# Battery_Board_v3_0.net
KiCad netlist of a schematic drawn in EAGLE
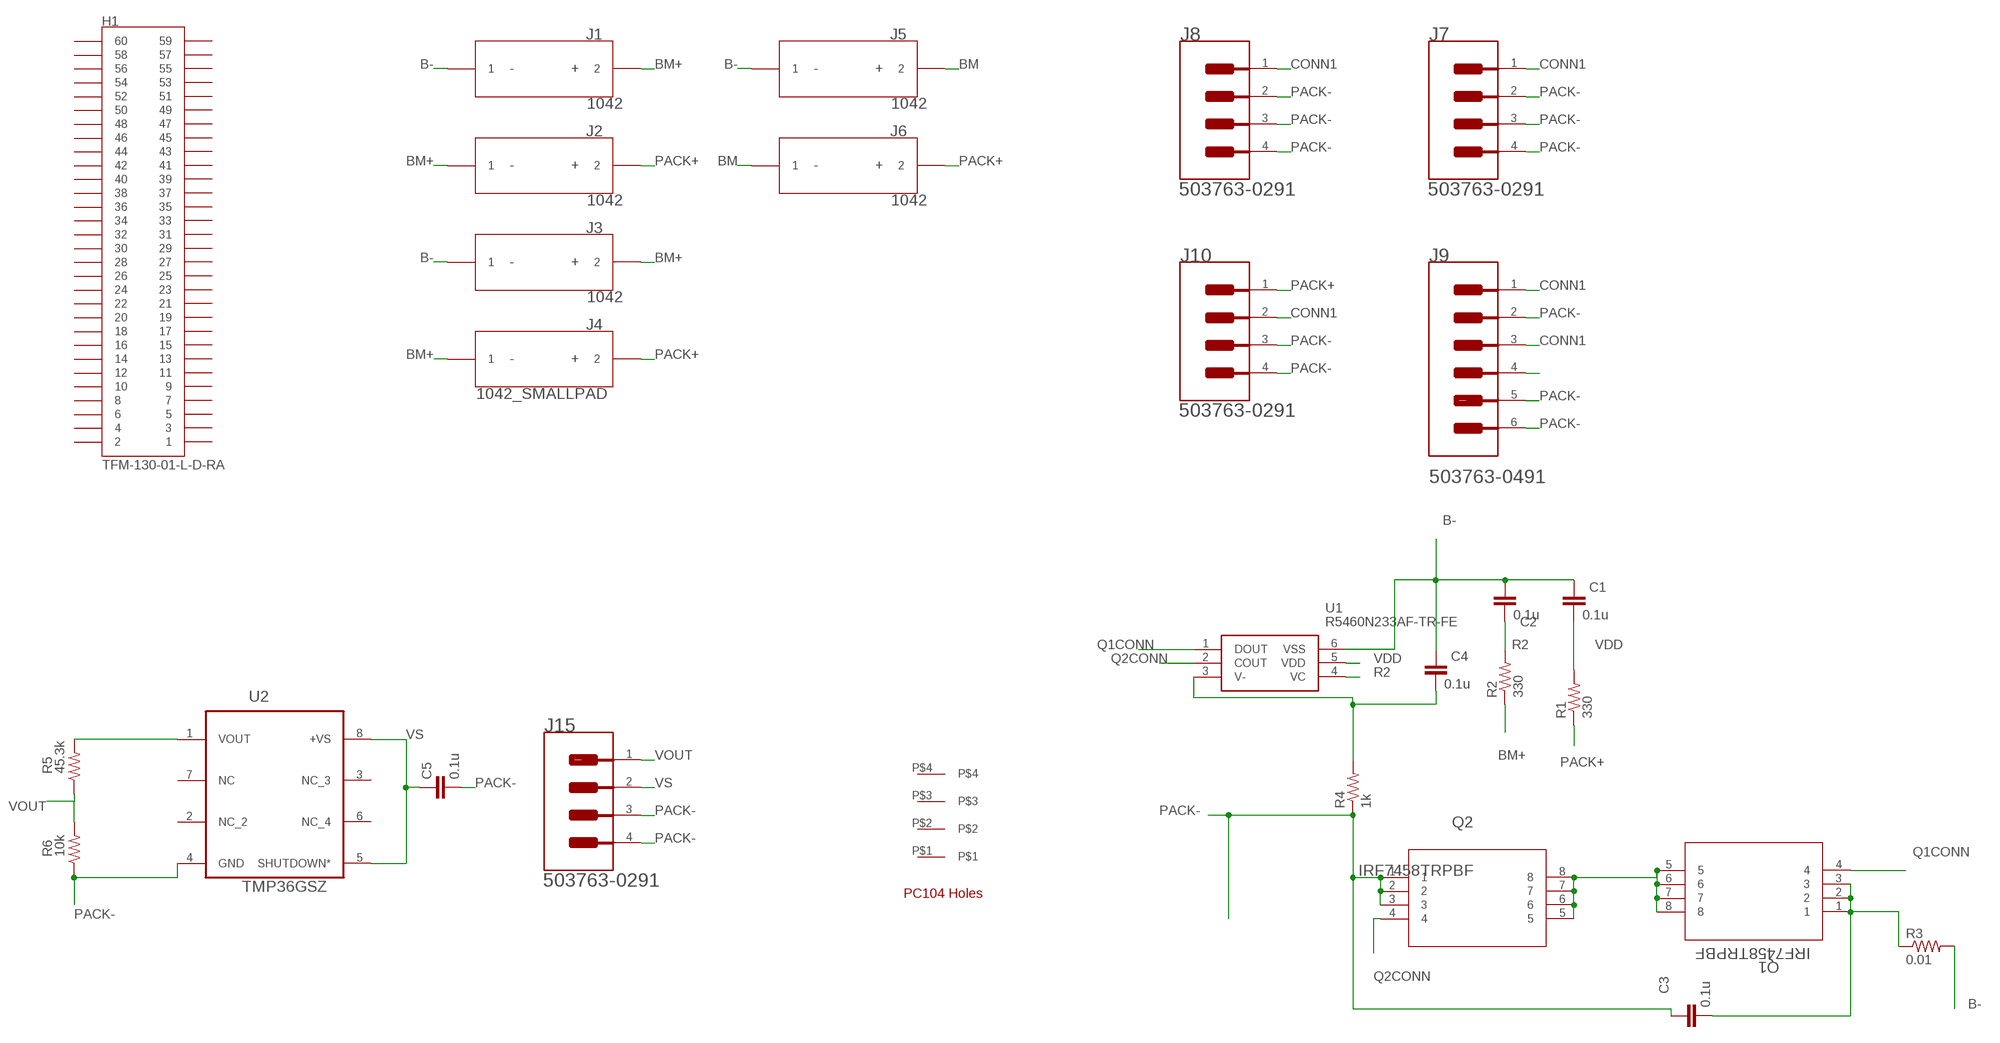
[diagram p0: schematic, sheet 1]

(export (version "E")
  (design (tool "Eeschema 10.0.6"))
  (components
    (comp (ref "C1")
      (value "0.1u")
      (footprint "eagle-import:0603-CAP")
      (libsource (lib "eagle-import") (part "CAP0603-CAP"))
    )
    (comp (ref "C2")
      (value "0.1u")
      (footprint "eagle-import:0603-CAP")
      (libsource (lib "eagle-import") (part "CAP0603-CAP"))
    )
    (comp (ref "C3")
      (value "0.1u")
      (footprint "eagle-import:0603-CAP")
      (libsource (lib "eagle-import") (part "CAP0603-CAP"))
    )
    (comp (ref "C4")
      (value "0.1u")
      (footprint "eagle-import:0603-CAP")
      (libsource (lib "eagle-import") (part "CAP0603-CAP"))
    )
    (comp (ref "C5")
      (value "0.1u")
      (footprint "eagle-import:0805")
      (libsource (lib "eagle-import") (part "CAP0805"))
    )
    (comp (ref "H1")
      (value "TFM-130-01-L-D-RA")
      (footprint "eagle-import:60_PIN")
      (libsource (lib "eagle-import") (part "TFM-130-01-L-D-RA"))
    )
    (comp (ref "J1")
      (value "1042")
      (footprint "eagle-import:1042_KEY")
      (fields (field (name "COPYRIGHT") "Copyright (C) 2021 Ultra Librarian. All rights reserved."))
      (libsource (lib "eagle-import") (part "1042"))
    )
    (comp (ref "J2")
      (value "1042")
      (footprint "eagle-import:1042_KEY")
      (fields (field (name "COPYRIGHT") "Copyright (C) 2021 Ultra Librarian. All rights reserved."))
      (libsource (lib "eagle-import") (part "1042"))
    )
    (comp (ref "J3")
      (value "1042")
      (footprint "eagle-import:1042_KEY")
      (fields (field (name "COPYRIGHT") "Copyright (C) 2021 Ultra Librarian. All rights reserved."))
      (libsource (lib "eagle-import") (part "1042"))
    )
    (comp (ref "J4")
      (value "1042_SMALLPAD")
      (footprint "eagle-import:1042_KEY_SMALLPAD")
      (libsource (lib "eagle-import") (part "1042_SMALLPAD"))
    )
    (comp (ref "J5")
      (value "1042")
      (footprint "eagle-import:1042_KEY")
      (fields (field (name "COPYRIGHT") "Copyright (C) 2021 Ultra Librarian. All rights reserved."))
      (libsource (lib "eagle-import") (part "1042"))
    )
    (comp (ref "J6")
      (value "1042")
      (footprint "eagle-import:1042_KEY")
      (fields (field (name "COPYRIGHT") "Copyright (C) 2021 Ultra Librarian. All rights reserved."))
      (libsource (lib "eagle-import") (part "1042"))
    )
    (comp (ref "J7")
      (value "MOLEX_503763-0291MOLEX_503763-0291_0_0")
      (footprint "eagle-import:MOLEX_503763-0291_0")
      (fields
        (field (name "DIGIKEY_PART_NUMBER") "WM10654CT-ND")
        (field (name "MF") "Molex")
        (field (name "MOUSER_PART_NUMBER") "538-503763-0291")
      )
      (libsource (lib "eagle-import") (part "MOLEX_503763-0291MOLEX_503763-0291_0_0"))
    )
    (comp (ref "J8")
      (value "MOLEX_503763-0291MOLEX_503763-0291_0_0")
      (footprint "eagle-import:MOLEX_503763-0291_0")
      (fields
        (field (name "DIGIKEY_PART_NUMBER") "WM10654CT-ND")
        (field (name "MF") "Molex")
        (field (name "MOUSER_PART_NUMBER") "538-503763-0291")
      )
      (libsource (lib "eagle-import") (part "MOLEX_503763-0291MOLEX_503763-0291_0_0"))
    )
    (comp (ref "J9")
      (value "MOLEX_503763-0491MOLEX_503763-0491_0_0")
      (footprint "eagle-import:MOLEX_503763-0491_0")
      (fields
        (field (name "DIGIKEY_PART_NUMBER") "WM10655CT-ND")
        (field (name "MF") "Molex")
        (field (name "MOUSER_PART_NUMBER") "538-503763-0491")
      )
      (libsource (lib "eagle-import") (part "MOLEX_503763-0491MOLEX_503763-0491_0_0"))
    )
    (comp (ref "J10")
      (value "MOLEX_503763-0291MOLEX_503763-0291_0_0")
      (footprint "eagle-import:MOLEX_503763-0291_0")
      (fields
        (field (name "DIGIKEY_PART_NUMBER") "WM10654CT-ND")
        (field (name "MF") "Molex")
        (field (name "MOUSER_PART_NUMBER") "538-503763-0291")
      )
      (libsource (lib "eagle-import") (part "MOLEX_503763-0291MOLEX_503763-0291_0_0"))
    )
    (comp (ref "J15")
      (value "MOLEX_503763-0291MOLEX_503763-0291_0_0")
      (footprint "eagle-import:MOLEX_503763-0291_0")
      (fields
        (field (name "DIGIKEY_PART_NUMBER") "WM10654CT-ND")
        (field (name "MF") "Molex")
        (field (name "MOUSER_PART_NUMBER") "538-503763-0291")
      )
      (libsource (lib "eagle-import") (part "MOLEX_503763-0291MOLEX_503763-0291_0_0"))
    )
    (comp (ref "Q1")
      (value "IRF7458TRPBF")
      (footprint "eagle-import:SO-8_IRF7458_3P9X4P9_INF")
      (fields (field (name "COPYRIGHT") "Copyright (C) 2021 Ultra Librarian. All rights reserved."))
      (libsource (lib "eagle-import") (part "IRF7458TRPBF"))
    )
    (comp (ref "Q2")
      (value "IRF7458TRPBF")
      (footprint "eagle-import:SO-8_IRF7458_3P9X4P9_INF")
      (fields (field (name "COPYRIGHT") "Copyright (C) 2021 Ultra Librarian. All rights reserved."))
      (libsource (lib "eagle-import") (part "IRF7458TRPBF"))
    )
    (comp (ref "R1")
      (value "330")
      (footprint "eagle-import:0603-RES")
      (libsource (lib "eagle-import") (part "RESISTOR0603-RES"))
    )
    (comp (ref "R2")
      (value "330")
      (footprint "eagle-import:0603-RES")
      (libsource (lib "eagle-import") (part "RESISTOR0603-RES"))
    )
    (comp (ref "R3")
      (value "0.01")
      (footprint "eagle-import:R2512")
      (libsource (lib "eagle-import") (part "RESISTOR2512"))
    )
    (comp (ref "R4")
      (value "1k")
      (footprint "eagle-import:0603-RES")
      (libsource (lib "eagle-import") (part "RESISTOR0603-RES"))
    )
    (comp (ref "R5")
      (value "45.3k")
      (footprint "eagle-import:0805")
      (libsource (lib "eagle-import") (part "RESISTOR0805-RES"))
    )
    (comp (ref "R6")
      (value "10k")
      (footprint "eagle-import:0805")
      (libsource (lib "eagle-import") (part "RESISTOR0805-RES"))
    )
    (comp (ref "U$1")
      (value "PC104_HOLES")
      (footprint "eagle-import:PC104_HOLES")
      (libsource (lib "eagle-import") (part "PC104_HOLES"))
    )
    (comp (ref "U1")
      (value "R5460N233AF-TR-FE")
      (footprint "eagle-import:SOT95P280X140-6N")
      (fields (field (name "MOUSER_PART_NUMBER") "848-R5460N233AFTRFE"))
      (libsource (lib "eagle-import") (part "R5460N233AF-TR-FE"))
    )
    (comp (ref "U2")
      (value "TMP36GSZ")
      (footprint "eagle-import:SOIC127P600X175-8N")
      (fields (field (name "MF") "Analog Devices"))
      (libsource (lib "eagle-import") (part "TMP36GSZ"))
    )
  )
  (nets
    (net (code "1") (name "/B-") (class "Default")
      (node (ref "C1") (pin "1") (pinfunction "1_1") (pintype "passive"))
      (node (ref "C2") (pin "1") (pinfunction "1_1") (pintype "passive"))
      (node (ref "C4") (pin "1") (pinfunction "1_1") (pintype "passive"))
      (node (ref "J1") (pin "1") (pinfunction "1_1") (pintype "passive"))
      (node (ref "J3") (pin "1") (pinfunction "1_1") (pintype "passive"))
      (node (ref "J5") (pin "1") (pinfunction "1_1") (pintype "passive"))
      (node (ref "R3") (pin "2") (pinfunction "2_2") (pintype "passive"))
      (node (ref "U1") (pin "6") (pinfunction "VSS_6") (pintype "bidirectional"))
    )
    (net (code "2") (name "/BM") (class "Default")
      (node (ref "J5") (pin "2") (pinfunction "2_2") (pintype "passive"))
      (node (ref "J6") (pin "1") (pinfunction "1_1") (pintype "passive"))
    )
    (net (code "3") (name "/BM+") (class "Default")
      (node (ref "J1") (pin "2") (pinfunction "2_2") (pintype "passive"))
      (node (ref "J2") (pin "1") (pinfunction "1_1") (pintype "passive"))
      (node (ref "J3") (pin "2") (pinfunction "2_2") (pintype "passive"))
      (node (ref "J4") (pin "1") (pinfunction "1_1") (pintype "passive"))
      (node (ref "R2") (pin "1") (pinfunction "1_1") (pintype "passive"))
    )
    (net (code "4") (name "/CONN1") (class "Default")
      (node (ref "J10") (pin "2") (pinfunction "2_2") (pintype "bidirectional"))
      (node (ref "J7") (pin "1") (pinfunction "1_1") (pintype "bidirectional"))
      (node (ref "J8") (pin "1") (pinfunction "1_1") (pintype "bidirectional"))
      (node (ref "J9") (pin "1") (pinfunction "1_1") (pintype "passive"))
      (node (ref "J9") (pin "3") (pinfunction "3_3") (pintype "passive"))
    )
    (net (code "5") (name "/PACK+") (class "Default")
      (node (ref "J10") (pin "1") (pinfunction "1_1") (pintype "bidirectional"))
      (node (ref "J2") (pin "2") (pinfunction "2_2") (pintype "passive"))
      (node (ref "J4") (pin "2") (pinfunction "2_2") (pintype "passive"))
      (node (ref "J6") (pin "2") (pinfunction "2_2") (pintype "passive"))
      (node (ref "R1") (pin "1") (pinfunction "1_1") (pintype "passive"))
    )
    (net (code "6") (name "/PACK-") (class "Default")
      (node (ref "C3") (pin "1") (pinfunction "1_1") (pintype "passive"))
      (node (ref "C5") (pin "2") (pinfunction "2_2") (pintype "passive"))
      (node (ref "J10") (pin "3") (pinfunction "MNT_1_3") (pintype "bidirectional"))
      (node (ref "J10") (pin "4") (pinfunction "MNT_2_4") (pintype "bidirectional"))
      (node (ref "J15") (pin "3") (pinfunction "MNT_1_3") (pintype "bidirectional"))
      (node (ref "J15") (pin "4") (pinfunction "MNT_2_4") (pintype "bidirectional"))
      (node (ref "J7") (pin "2") (pinfunction "2_2") (pintype "bidirectional"))
      (node (ref "J7") (pin "3") (pinfunction "MNT_1_3") (pintype "bidirectional"))
      (node (ref "J7") (pin "4") (pinfunction "MNT_2_4") (pintype "bidirectional"))
      (node (ref "J8") (pin "2") (pinfunction "2_2") (pintype "bidirectional"))
      (node (ref "J8") (pin "3") (pinfunction "MNT_1_3") (pintype "bidirectional"))
      (node (ref "J8") (pin "4") (pinfunction "MNT_2_4") (pintype "bidirectional"))
      (node (ref "J9") (pin "2") (pinfunction "2_2") (pintype "passive"))
      (node (ref "J9") (pin "4") (pinfunction "4_4") (pintype "passive"))
      (node (ref "J9") (pin "5") (pinfunction "MNT_1_5") (pintype "passive"))
      (node (ref "J9") (pin "6") (pinfunction "MNT_2_6") (pintype "passive"))
      (node (ref "Q2") (pin "1") (pinfunction "1_1") (pintype "passive"))
      (node (ref "Q2") (pin "2") (pinfunction "2_2") (pintype "passive"))
      (node (ref "Q2") (pin "3") (pinfunction "3_3") (pintype "passive"))
      (node (ref "R4") (pin "1") (pinfunction "1_1") (pintype "passive"))
      (node (ref "R6") (pin "1") (pinfunction "1_1") (pintype "passive"))
      (node (ref "U2") (pin "4") (pinfunction "GND_4") (pintype "passive"))
    )
    (net (code "7") (name "/Q1CONN") (class "Default")
      (node (ref "Q1") (pin "4") (pinfunction "4_4") (pintype "passive"))
      (node (ref "U1") (pin "1") (pinfunction "DOUT_1") (pintype "bidirectional"))
    )
    (net (code "8") (name "/Q2CONN") (class "Default")
      (node (ref "Q2") (pin "4") (pinfunction "4_4") (pintype "passive"))
      (node (ref "U1") (pin "2") (pinfunction "COUT_2") (pintype "bidirectional"))
    )
    (net (code "9") (name "/R2") (class "Default")
      (node (ref "C2") (pin "2") (pinfunction "2_2") (pintype "passive"))
      (node (ref "R2") (pin "2") (pinfunction "2_2") (pintype "passive"))
      (node (ref "U1") (pin "4") (pinfunction "VC_4") (pintype "bidirectional"))
    )
    (net (code "10") (name "/VDD") (class "Default")
      (node (ref "C1") (pin "2") (pinfunction "2_2") (pintype "passive"))
      (node (ref "R1") (pin "2") (pinfunction "2_2") (pintype "passive"))
      (node (ref "U1") (pin "5") (pinfunction "VDD_5") (pintype "bidirectional"))
    )
    (net (code "11") (name "/VOUT") (class "Default")
      (node (ref "J15") (pin "1") (pinfunction "1_1") (pintype "bidirectional"))
      (node (ref "R5") (pin "1") (pinfunction "1_1") (pintype "passive"))
      (node (ref "R6") (pin "2") (pinfunction "2_2") (pintype "passive"))
    )
    (net (code "12") (name "/VS") (class "Default")
      (node (ref "C5") (pin "1") (pinfunction "1_1") (pintype "passive"))
      (node (ref "J15") (pin "2") (pinfunction "2_2") (pintype "bidirectional"))
      (node (ref "U2") (pin "5") (pinfunction "SHUTDOWN*_5") (pintype "passive"))
      (node (ref "U2") (pin "8") (pinfunction "+VS_8") (pintype "power_in"))
    )
    (net (code "13") (name "Net-(C3-Pad2)") (class "Default")
      (node (ref "C3") (pin "2") (pinfunction "2_2") (pintype "passive"))
      (node (ref "Q1") (pin "1") (pinfunction "1_1") (pintype "passive"))
      (node (ref "Q1") (pin "2") (pinfunction "2_2") (pintype "passive"))
      (node (ref "Q1") (pin "3") (pinfunction "3_3") (pintype "passive"))
      (node (ref "R3") (pin "1") (pinfunction "1_1") (pintype "passive"))
    )
    (net (code "14") (name "Net-(Q1-Pad5)") (class "Default")
      (node (ref "Q1") (pin "5") (pinfunction "5_5") (pintype "passive"))
      (node (ref "Q1") (pin "6") (pinfunction "6_6") (pintype "passive"))
      (node (ref "Q1") (pin "7") (pinfunction "7_7") (pintype "passive"))
      (node (ref "Q1") (pin "8") (pinfunction "8_8") (pintype "passive"))
      (node (ref "Q2") (pin "5") (pinfunction "5_5") (pintype "passive"))
      (node (ref "Q2") (pin "6") (pinfunction "6_6") (pintype "passive"))
      (node (ref "Q2") (pin "7") (pinfunction "7_7") (pintype "passive"))
      (node (ref "Q2") (pin "8") (pinfunction "8_8") (pintype "passive"))
    )
    (net (code "15") (name "Net-(U1-V-)") (class "Default")
      (node (ref "C4") (pin "2") (pinfunction "2_2") (pintype "passive"))
      (node (ref "R4") (pin "2") (pinfunction "2_2") (pintype "passive"))
      (node (ref "U1") (pin "3") (pinfunction "V-_3") (pintype "bidirectional"))
    )
    (net (code "16") (name "Net-(U2-VOUT)") (class "Default")
      (node (ref "R5") (pin "2") (pinfunction "2_2") (pintype "passive"))
      (node (ref "U2") (pin "1") (pinfunction "VOUT_1") (pintype "passive"))
    )
    (net (code "17") (name "unconnected-(H1-Pad1)") (class "Default")
      (node (ref "H1") (pin "1") (pinfunction "1_1") (pintype "bidirectional"))
    )
    (net (code "18") (name "unconnected-(H1-Pad2)") (class "Default")
      (node (ref "H1") (pin "2") (pinfunction "2_2") (pintype "bidirectional"))
    )
    (net (code "19") (name "unconnected-(H1-Pad3)") (class "Default")
      (node (ref "H1") (pin "3") (pinfunction "3_3") (pintype "bidirectional"))
    )
    (net (code "20") (name "unconnected-(H1-Pad4)") (class "Default")
      (node (ref "H1") (pin "4") (pinfunction "4_4") (pintype "bidirectional"))
    )
    (net (code "21") (name "unconnected-(H1-Pad5)") (class "Default")
      (node (ref "H1") (pin "5") (pinfunction "5_5") (pintype "bidirectional"))
    )
    (net (code "22") (name "unconnected-(H1-Pad6)") (class "Default")
      (node (ref "H1") (pin "6") (pinfunction "6_6") (pintype "bidirectional"))
    )
    (net (code "23") (name "unconnected-(H1-Pad7)") (class "Default")
      (node (ref "H1") (pin "7") (pinfunction "7_7") (pintype "bidirectional"))
    )
    (net (code "24") (name "unconnected-(H1-Pad8)") (class "Default")
      (node (ref "H1") (pin "8") (pinfunction "8_8") (pintype "bidirectional"))
    )
    (net (code "25") (name "unconnected-(H1-Pad9)") (class "Default")
      (node (ref "H1") (pin "9") (pinfunction "9_9") (pintype "bidirectional"))
    )
    (net (code "26") (name "unconnected-(H1-Pad10)") (class "Default")
      (node (ref "H1") (pin "10") (pinfunction "10_10") (pintype "bidirectional"))
    )
    (net (code "27") (name "unconnected-(H1-Pad11)") (class "Default")
      (node (ref "H1") (pin "11") (pinfunction "11_11") (pintype "bidirectional"))
    )
    (net (code "28") (name "unconnected-(H1-Pad12)") (class "Default")
      (node (ref "H1") (pin "12") (pinfunction "12_12") (pintype "bidirectional"))
    )
    (net (code "29") (name "unconnected-(H1-Pad13)") (class "Default")
      (node (ref "H1") (pin "13") (pinfunction "13_13") (pintype "bidirectional"))
    )
    (net (code "30") (name "unconnected-(H1-Pad14)") (class "Default")
      (node (ref "H1") (pin "14") (pinfunction "14_14") (pintype "bidirectional"))
    )
    (net (code "31") (name "unconnected-(H1-Pad15)") (class "Default")
      (node (ref "H1") (pin "15") (pinfunction "15_15") (pintype "bidirectional"))
    )
    (net (code "32") (name "unconnected-(H1-Pad16)") (class "Default")
      (node (ref "H1") (pin "16") (pinfunction "16_16") (pintype "bidirectional"))
    )
    (net (code "33") (name "unconnected-(H1-Pad17)") (class "Default")
      (node (ref "H1") (pin "17") (pinfunction "17_17") (pintype "bidirectional"))
    )
    (net (code "34") (name "unconnected-(H1-Pad18)") (class "Default")
      (node (ref "H1") (pin "18") (pinfunction "18_18") (pintype "bidirectional"))
    )
    (net (code "35") (name "unconnected-(H1-Pad19)") (class "Default")
      (node (ref "H1") (pin "19") (pinfunction "19_19") (pintype "bidirectional"))
    )
    (net (code "36") (name "unconnected-(H1-Pad20)") (class "Default")
      (node (ref "H1") (pin "20") (pinfunction "20_20") (pintype "bidirectional"))
    )
    (net (code "37") (name "unconnected-(H1-Pad21)") (class "Default")
      (node (ref "H1") (pin "21") (pinfunction "21_21") (pintype "bidirectional"))
    )
    (net (code "38") (name "unconnected-(H1-Pad22)") (class "Default")
      (node (ref "H1") (pin "22") (pinfunction "22_22") (pintype "bidirectional"))
    )
    (net (code "39") (name "unconnected-(H1-Pad23)") (class "Default")
      (node (ref "H1") (pin "23") (pinfunction "23_23") (pintype "bidirectional"))
    )
    (net (code "40") (name "unconnected-(H1-Pad24)") (class "Default")
      (node (ref "H1") (pin "24") (pinfunction "24_24") (pintype "bidirectional"))
    )
    (net (code "41") (name "unconnected-(H1-Pad25)") (class "Default")
      (node (ref "H1") (pin "25") (pinfunction "25_25") (pintype "bidirectional"))
    )
    (net (code "42") (name "unconnected-(H1-Pad26)") (class "Default")
      (node (ref "H1") (pin "26") (pinfunction "26_26") (pintype "bidirectional"))
    )
    (net (code "43") (name "unconnected-(H1-Pad27)") (class "Default")
      (node (ref "H1") (pin "27") (pinfunction "27_27") (pintype "bidirectional"))
    )
    (net (code "44") (name "unconnected-(H1-Pad28)") (class "Default")
      (node (ref "H1") (pin "28") (pinfunction "28_28") (pintype "bidirectional"))
    )
    (net (code "45") (name "unconnected-(H1-Pad29)") (class "Default")
      (node (ref "H1") (pin "29") (pinfunction "29_29") (pintype "bidirectional"))
    )
    (net (code "46") (name "unconnected-(H1-Pad30)") (class "Default")
      (node (ref "H1") (pin "30") (pinfunction "30_30") (pintype "bidirectional"))
    )
    (net (code "47") (name "unconnected-(H1-Pad31)") (class "Default")
      (node (ref "H1") (pin "31") (pinfunction "31_31") (pintype "bidirectional"))
    )
    (net (code "48") (name "unconnected-(H1-Pad32)") (class "Default")
      (node (ref "H1") (pin "32") (pinfunction "32_32") (pintype "bidirectional"))
    )
    (net (code "49") (name "unconnected-(H1-Pad33)") (class "Default")
      (node (ref "H1") (pin "33") (pinfunction "33_33") (pintype "bidirectional"))
    )
    (net (code "50") (name "unconnected-(H1-Pad34)") (class "Default")
      (node (ref "H1") (pin "34") (pinfunction "34_34") (pintype "bidirectional"))
    )
    (net (code "51") (name "unconnected-(H1-Pad35)") (class "Default")
      (node (ref "H1") (pin "35") (pinfunction "35_35") (pintype "bidirectional"))
    )
    (net (code "52") (name "unconnected-(H1-Pad36)") (class "Default")
      (node (ref "H1") (pin "36") (pinfunction "36_36") (pintype "bidirectional"))
    )
    (net (code "53") (name "unconnected-(H1-Pad37)") (class "Default")
      (node (ref "H1") (pin "37") (pinfunction "37_37") (pintype "bidirectional"))
    )
    (net (code "54") (name "unconnected-(H1-Pad38)") (class "Default")
      (node (ref "H1") (pin "38") (pinfunction "38_38") (pintype "bidirectional"))
    )
    (net (code "55") (name "unconnected-(H1-Pad39)") (class "Default")
      (node (ref "H1") (pin "39") (pinfunction "39_39") (pintype "bidirectional"))
    )
    (net (code "56") (name "unconnected-(H1-Pad40)") (class "Default")
      (node (ref "H1") (pin "40") (pinfunction "40_40") (pintype "bidirectional"))
    )
    (net (code "57") (name "unconnected-(H1-Pad41)") (class "Default")
      (node (ref "H1") (pin "41") (pinfunction "41_41") (pintype "bidirectional"))
    )
    (net (code "58") (name "unconnected-(H1-Pad42)") (class "Default")
      (node (ref "H1") (pin "42") (pinfunction "42_42") (pintype "bidirectional"))
    )
    (net (code "59") (name "unconnected-(H1-Pad43)") (class "Default")
      (node (ref "H1") (pin "43") (pinfunction "43_43") (pintype "bidirectional"))
    )
    (net (code "60") (name "unconnected-(H1-Pad44)") (class "Default")
      (node (ref "H1") (pin "44") (pinfunction "44_44") (pintype "bidirectional"))
    )
    (net (code "61") (name "unconnected-(H1-Pad45)") (class "Default")
      (node (ref "H1") (pin "45") (pinfunction "45_45") (pintype "bidirectional"))
    )
    (net (code "62") (name "unconnected-(H1-Pad46)") (class "Default")
      (node (ref "H1") (pin "46") (pinfunction "46_46") (pintype "bidirectional"))
    )
    (net (code "63") (name "unconnected-(H1-Pad47)") (class "Default")
      (node (ref "H1") (pin "47") (pinfunction "47_47") (pintype "bidirectional"))
    )
    (net (code "64") (name "unconnected-(H1-Pad48)") (class "Default")
      (node (ref "H1") (pin "48") (pinfunction "48_48") (pintype "bidirectional"))
    )
    (net (code "65") (name "unconnected-(H1-Pad49)") (class "Default")
      (node (ref "H1") (pin "49") (pinfunction "49_49") (pintype "bidirectional"))
    )
    (net (code "66") (name "unconnected-(H1-Pad50)") (class "Default")
      (node (ref "H1") (pin "50") (pinfunction "50_50") (pintype "bidirectional"))
    )
    (net (code "67") (name "unconnected-(H1-Pad51)") (class "Default")
      (node (ref "H1") (pin "51") (pinfunction "51_51") (pintype "bidirectional"))
    )
    (net (code "68") (name "unconnected-(H1-Pad52)") (class "Default")
      (node (ref "H1") (pin "52") (pinfunction "52_52") (pintype "bidirectional"))
    )
    (net (code "69") (name "unconnected-(H1-Pad53)") (class "Default")
      (node (ref "H1") (pin "53") (pinfunction "53_53") (pintype "bidirectional"))
    )
    (net (code "70") (name "unconnected-(H1-Pad54)") (class "Default")
      (node (ref "H1") (pin "54") (pinfunction "54_54") (pintype "bidirectional"))
    )
    (net (code "71") (name "unconnected-(H1-Pad55)") (class "Default")
      (node (ref "H1") (pin "55") (pinfunction "55_55") (pintype "bidirectional"))
    )
    (net (code "72") (name "unconnected-(H1-Pad56)") (class "Default")
      (node (ref "H1") (pin "56") (pinfunction "56_56") (pintype "bidirectional"))
    )
    (net (code "73") (name "unconnected-(H1-Pad57)") (class "Default")
      (node (ref "H1") (pin "57") (pinfunction "57_57") (pintype "bidirectional"))
    )
    (net (code "74") (name "unconnected-(H1-Pad58)") (class "Default")
      (node (ref "H1") (pin "58") (pinfunction "58_58") (pintype "bidirectional"))
    )
    (net (code "75") (name "unconnected-(H1-Pad59)") (class "Default")
      (node (ref "H1") (pin "59") (pinfunction "59_59") (pintype "bidirectional"))
    )
    (net (code "76") (name "unconnected-(H1-Pad60)") (class "Default")
      (node (ref "H1") (pin "60") (pinfunction "60_60") (pintype "bidirectional"))
    )
    (net (code "77") (name "unconnected-(U$1-PadP$1)") (class "Default")
      (node (ref "U$1") (pin "P$1") (pinfunction "P$1_P$1") (pintype "bidirectional"))
    )
    (net (code "78") (name "unconnected-(U$1-PadP$2)") (class "Default")
      (node (ref "U$1") (pin "P$2") (pinfunction "P$2_P$2") (pintype "bidirectional"))
    )
    (net (code "79") (name "unconnected-(U$1-PadP$3)") (class "Default")
      (node (ref "U$1") (pin "P$3") (pinfunction "P$3_P$3") (pintype "bidirectional"))
    )
    (net (code "80") (name "unconnected-(U$1-PadP$4)") (class "Default")
      (node (ref "U$1") (pin "P$4") (pinfunction "P$4_P$4") (pintype "bidirectional"))
    )
    (net (code "81") (name "unconnected-(U2-NC-Pad7)") (class "Default")
      (node (ref "U2") (pin "7") (pinfunction "NC_7") (pintype "passive"))
    )
    (net (code "82") (name "unconnected-(U2-NC_2-Pad2)") (class "Default")
      (node (ref "U2") (pin "2") (pinfunction "NC_2_2") (pintype "passive"))
    )
    (net (code "83") (name "unconnected-(U2-NC_3-Pad3)") (class "Default")
      (node (ref "U2") (pin "3") (pinfunction "NC_3_3") (pintype "passive"))
    )
    (net (code "84") (name "unconnected-(U2-NC_4-Pad6)") (class "Default")
      (node (ref "U2") (pin "6") (pinfunction "NC_4_6") (pintype "passive"))
    )
  )
)
